# S7CAS-PLEIADES-CARTE-MERE_P02_POWER_CARR.net
KiCad netlist of a schematic drawn in Altium Designer
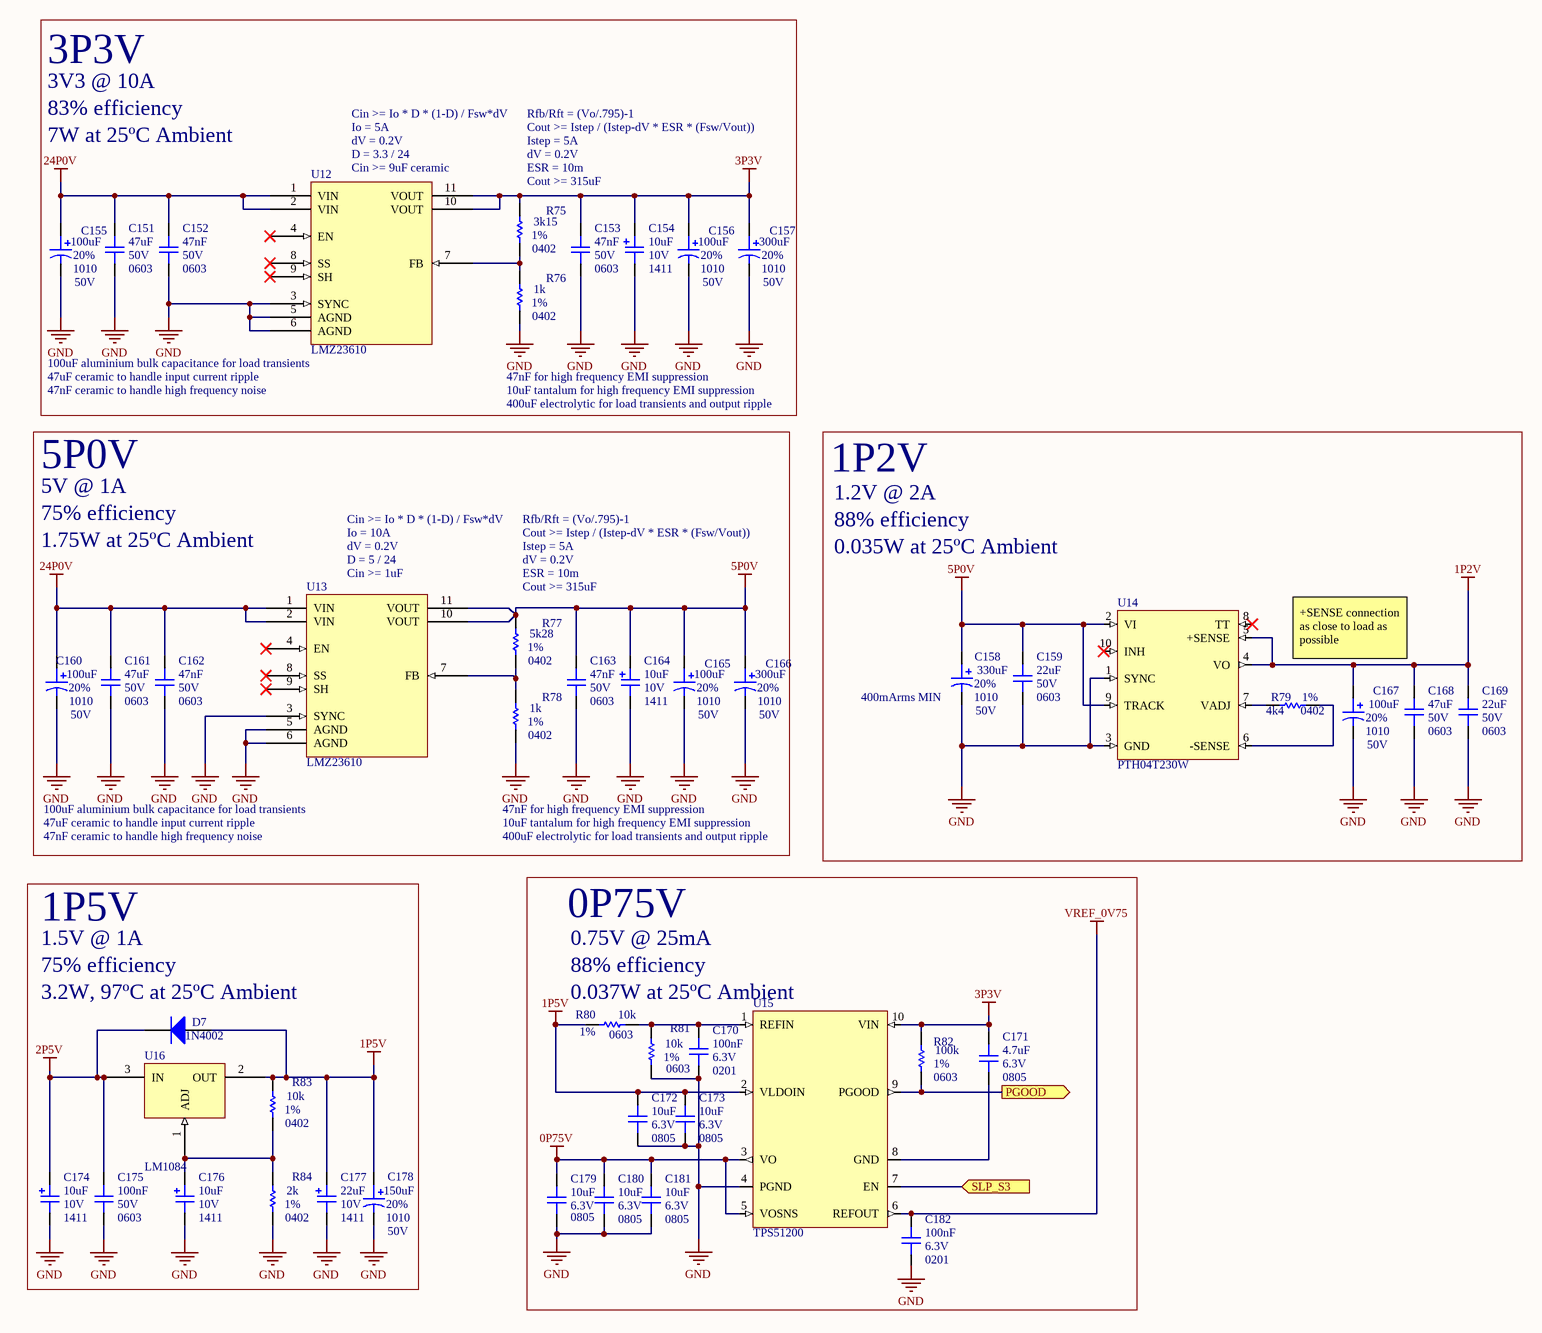
[diagram p0: S7CAS-PLEIADES-CARTE-MERE_P02_POWER_CARRIER.SchDoc]

(export (version "E")
  (design (tool "Eeschema 10.0.6"))
  (components
    (comp (ref "C151")
      (value "47uF")
      (footprint "CAP_0603")
      (description "CAP - 0603")
      (fields
        (field (name "VOLTAGE") "50V")
        (field (name "PACKAGE") "0603")
        (field (name "CREATEDBY") "Jonathan Bouchard")
      )
      (libsource (lib "S7CAS_Lib2019_REV1_00") (part "CAP - 0603"))
    )
    (comp (ref "C152")
      (value "47nF")
      (footprint "CAP_0603")
      (description "CAP - 0603")
      (fields
        (field (name "VOLTAGE") "50V")
        (field (name "PACKAGE") "0603")
        (field (name "CREATEDBY") "Jonathan Bouchard")
      )
      (libsource (lib "S7CAS_Lib2019_REV1_00") (part "CAP - 0603"))
    )
    (comp (ref "C153")
      (value "47nF")
      (footprint "CAP_0603")
      (description "CAP - 0603")
      (fields
        (field (name "VOLTAGE") "50V")
        (field (name "PACKAGE") "0603")
        (field (name "CREATEDBY") "Jonathan Bouchard")
      )
      (libsource (lib "S7CAS_Lib2019_REV1_00") (part "CAP - 0603"))
    )
    (comp (ref "C154")
      (value "10uF")
      (footprint "CAP_TAN_1411(B)")
      (description "CAP - TANTALUM - 1411")
      (fields
        (field (name "VOLTAGE") "10V")
        (field (name "PACKAGE") "1411")
        (field (name "Comment") "CAP - TANTALUM - CASE B")
        (field (name "CREATEDBY") "Jonathan Bouchard")
      )
      (libsource (lib "S7CAS_Lib2019_REV1_00") (part "CAP_TANT_1411(B)"))
    )
    (comp (ref "C155")
      (value "100uF")
      (footprint "CAP_ALU_1010_vishay")
      (description "CAP - ALU 100uF 20% 50V - 1010")
      (fields
        (field (name "MFG") "Vishay Dale")
        (field (name "MFG PART NUMBER") "MAL215099101E3")
        (field (name "VOLTAGE") "50V")
        (field (name "PACKAGE") "1010")
        (field (name "PRECISION") "20%")
        (field (name "CREATEDBY") "Jonathan Bouchard")
      )
      (libsource (lib "S7CAS_Lib2019_REV1_00") (part "CAP_ALU_MAL215099101E3"))
    )
    (comp (ref "C156")
      (value "100uF")
      (footprint "CAP_ALU_1010_vishay")
      (description "CAP - ALU 100uF 20% 50V - 1010")
      (fields
        (field (name "MFG") "Vishay Dale")
        (field (name "MFG PART NUMBER") "MAL215099101E3")
        (field (name "VOLTAGE") "50V")
        (field (name "PACKAGE") "1010")
        (field (name "PRECISION") "20%")
        (field (name "CREATEDBY") "Jonathan Bouchard")
      )
      (libsource (lib "S7CAS_Lib2019_REV1_00") (part "CAP_ALU_MAL215099101E3"))
    )
    (comp (ref "C157")
      (value "300uF")
      (footprint "CAP_ALU_1010_vishay")
      (description "CAP - ALU 100uF 20% 50V - 1010")
      (fields
        (field (name "MFG") "Vishay Dale")
        (field (name "MFG PART NUMBER") "MAL215099101E3")
        (field (name "VOLTAGE") "50V")
        (field (name "PACKAGE") "1010")
        (field (name "PRECISION") "20%")
        (field (name "CREATEDBY") "Jonathan Bouchard")
      )
      (libsource (lib "S7CAS_Lib2019_REV1_00") (part "CAP_ALU_MAL215099101E3"))
    )
    (comp (ref "C158")
      (value "330uF")
      (footprint "CAP_ALU_1010_vishay")
      (description "CAP - ALU 100uF 20% 50V - 1010")
      (fields
        (field (name "MFG") "Vishay Dale")
        (field (name "MFG PART NUMBER") "MAL215099101E3")
        (field (name "VOLTAGE") "50V")
        (field (name "PACKAGE") "1010")
        (field (name "PRECISION") "20%")
        (field (name "CREATEDBY") "Jonathan Bouchard")
      )
      (libsource (lib "S7CAS_Lib2019_REV1_00") (part "CAP_ALU_MAL215099101E3"))
    )
    (comp (ref "C159")
      (value "22uF")
      (footprint "CAP_0603")
      (description "CAP - 0603")
      (fields
        (field (name "VOLTAGE") "50V")
        (field (name "PACKAGE") "0603")
        (field (name "CREATEDBY") "Jonathan Bouchard")
      )
      (libsource (lib "S7CAS_Lib2019_REV1_00") (part "CAP - 0603"))
    )
    (comp (ref "C160")
      (value "100uF")
      (footprint "CAP_ALU_1010_vishay")
      (description "CAP - ALU 100uF 20% 50V - 1010")
      (fields
        (field (name "MFG") "Vishay Dale")
        (field (name "MFG PART NUMBER") "MAL215099101E3")
        (field (name "VOLTAGE") "50V")
        (field (name "PACKAGE") "1010")
        (field (name "PRECISION") "20%")
        (field (name "CREATEDBY") "Jonathan Bouchard")
      )
      (libsource (lib "S7CAS_Lib2019_REV1_00") (part "CAP_ALU_MAL215099101E3"))
    )
    (comp (ref "C161")
      (value "47uF")
      (footprint "CAP_0603")
      (description "CAP - 0603")
      (fields
        (field (name "VOLTAGE") "50V")
        (field (name "PACKAGE") "0603")
        (field (name "CREATEDBY") "Jonathan Bouchard")
      )
      (libsource (lib "S7CAS_Lib2019_REV1_00") (part "CAP - 0603"))
    )
    (comp (ref "C162")
      (value "47nF")
      (footprint "CAP_0603")
      (description "CAP - 0603")
      (fields
        (field (name "VOLTAGE") "50V")
        (field (name "PACKAGE") "0603")
        (field (name "CREATEDBY") "Jonathan Bouchard")
      )
      (libsource (lib "S7CAS_Lib2019_REV1_00") (part "CAP - 0603"))
    )
    (comp (ref "C163")
      (value "47nF")
      (footprint "CAP_0603")
      (description "CAP - 0603")
      (fields
        (field (name "VOLTAGE") "50V")
        (field (name "PACKAGE") "0603")
        (field (name "CREATEDBY") "Jonathan Bouchard")
      )
      (libsource (lib "S7CAS_Lib2019_REV1_00") (part "CAP - 0603"))
    )
    (comp (ref "C164")
      (value "10uF")
      (footprint "CAP_TAN_1411(B)")
      (description "CAP - TANTALUM - 1411")
      (fields
        (field (name "VOLTAGE") "10V")
        (field (name "PACKAGE") "1411")
        (field (name "Comment") "CAP - TANTALUM - CASE B")
        (field (name "CREATEDBY") "Jonathan Bouchard")
      )
      (libsource (lib "S7CAS_Lib2019_REV1_00") (part "CAP_TANT_1411(B)"))
    )
    (comp (ref "C165")
      (value "100uF")
      (footprint "CAP_ALU_1010_vishay")
      (description "CAP - ALU 100uF 20% 50V - 1010")
      (fields
        (field (name "MFG") "Vishay Dale")
        (field (name "MFG PART NUMBER") "MAL215099101E3")
        (field (name "VOLTAGE") "50V")
        (field (name "PACKAGE") "1010")
        (field (name "PRECISION") "20%")
        (field (name "CREATEDBY") "Jonathan Bouchard")
      )
      (libsource (lib "S7CAS_Lib2019_REV1_00") (part "CAP_ALU_MAL215099101E3"))
    )
    (comp (ref "C166")
      (value "300uF")
      (footprint "CAP_ALU_1010_vishay")
      (description "CAP - ALU 100uF 20% 50V - 1010")
      (fields
        (field (name "MFG") "Vishay Dale")
        (field (name "MFG PART NUMBER") "MAL215099101E3")
        (field (name "VOLTAGE") "50V")
        (field (name "PACKAGE") "1010")
        (field (name "PRECISION") "20%")
        (field (name "CREATEDBY") "Jonathan Bouchard")
      )
      (libsource (lib "S7CAS_Lib2019_REV1_00") (part "CAP_ALU_MAL215099101E3"))
    )
    (comp (ref "C167")
      (value "100uF")
      (footprint "CAP_ALU_1010_vishay")
      (description "CAP - ALU 100uF 20% 50V - 1010")
      (fields
        (field (name "MFG") "Vishay Dale")
        (field (name "MFG PART NUMBER") "MAL215099101E3")
        (field (name "VOLTAGE") "50V")
        (field (name "PACKAGE") "1010")
        (field (name "PRECISION") "20%")
        (field (name "CREATEDBY") "Jonathan Bouchard")
      )
      (libsource (lib "S7CAS_Lib2019_REV1_00") (part "CAP_ALU_MAL215099101E3"))
    )
    (comp (ref "C168")
      (value "47uF")
      (footprint "CAP_0603")
      (description "CAP - 0603")
      (fields
        (field (name "VOLTAGE") "50V")
        (field (name "PACKAGE") "0603")
        (field (name "CREATEDBY") "Jonathan Bouchard")
      )
      (libsource (lib "S7CAS_Lib2019_REV1_00") (part "CAP - 0603"))
    )
    (comp (ref "C169")
      (value "22uF")
      (footprint "CAP_0603")
      (description "CAP - 0603")
      (fields
        (field (name "VOLTAGE") "50V")
        (field (name "PACKAGE") "0603")
        (field (name "CREATEDBY") "Jonathan Bouchard")
      )
      (libsource (lib "S7CAS_Lib2019_REV1_00") (part "CAP - 0603"))
    )
    (comp (ref "C170")
      (value "100nF")
      (footprint "CAP_0201")
      (description "CAP - 0201")
      (fields
        (field (name "VOLTAGE") "6.3V")
        (field (name "PACKAGE") "0201")
        (field (name "CREATEDBY") "Jonathan Bouchard")
      )
      (libsource (lib "S7CAS_Lib2019_REV1_00") (part "CAP - 0201"))
    )
    (comp (ref "C171")
      (value "4.7uF")
      (footprint "CAP_0805")
      (description "CAP - 0805")
      (fields
        (field (name "VOLTAGE") "6.3V")
        (field (name "PACKAGE") "0805")
        (field (name "CREATEDBY") "Jonathan Bouchard")
      )
      (libsource (lib "S7CAS_Lib2019_REV1_00") (part "CAP - 0805"))
    )
    (comp (ref "C172")
      (value "10uF")
      (footprint "CAP_0805")
      (description "CAP - 0805")
      (fields
        (field (name "VOLTAGE") "6.3V")
        (field (name "PACKAGE") "0805")
        (field (name "CREATEDBY") "Jonathan Bouchard")
      )
      (libsource (lib "S7CAS_Lib2019_REV1_00") (part "CAP - 0805"))
    )
    (comp (ref "C173")
      (value "10uF")
      (footprint "CAP_0805")
      (description "CAP - 0805")
      (fields
        (field (name "VOLTAGE") "6.3V")
        (field (name "PACKAGE") "0805")
        (field (name "CREATEDBY") "Jonathan Bouchard")
      )
      (libsource (lib "S7CAS_Lib2019_REV1_00") (part "CAP - 0805"))
    )
    (comp (ref "C174")
      (value "10uF")
      (footprint "CAP_TAN_1411(B)")
      (description "CAP - TANTALUM - 1411")
      (fields
        (field (name "VOLTAGE") "10V")
        (field (name "PACKAGE") "1411")
        (field (name "Comment") "CAP - TANTALUM - CASE B")
        (field (name "CREATEDBY") "Jonathan Bouchard")
      )
      (libsource (lib "S7CAS_Lib2019_REV1_00") (part "CAP_TANT_1411(B)"))
    )
    (comp (ref "C175")
      (value "100nF")
      (footprint "CAP_0603")
      (description "CAP - 0603")
      (fields
        (field (name "VOLTAGE") "50V")
        (field (name "PACKAGE") "0603")
        (field (name "CREATEDBY") "Jonathan Bouchard")
      )
      (libsource (lib "S7CAS_Lib2019_REV1_00") (part "CAP - 0603"))
    )
    (comp (ref "C176")
      (value "10uF")
      (footprint "CAP_TAN_1411(B)")
      (description "CAP - TANTALUM - 1411")
      (fields
        (field (name "VOLTAGE") "10V")
        (field (name "PACKAGE") "1411")
        (field (name "Comment") "CAP - TANTALUM - CASE B")
        (field (name "CREATEDBY") "Jonathan Bouchard")
      )
      (libsource (lib "S7CAS_Lib2019_REV1_00") (part "CAP_TANT_1411(B)"))
    )
    (comp (ref "C177")
      (value "22uF")
      (footprint "CAP_TAN_1411(B)")
      (description "CAP - TANTALUM - 1411")
      (fields
        (field (name "VOLTAGE") "10V")
        (field (name "PACKAGE") "1411")
        (field (name "Comment") "CAP - TANTALUM - CASE B")
        (field (name "CREATEDBY") "Jonathan Bouchard")
      )
      (libsource (lib "S7CAS_Lib2019_REV1_00") (part "CAP_TANT_1411(B)"))
    )
    (comp (ref "C178")
      (value "150uF")
      (footprint "CAP_ALU_1010_vishay")
      (description "CAP - ALU 100uF 20% 50V - 1010")
      (fields
        (field (name "MFG") "Vishay Dale")
        (field (name "MFG PART NUMBER") "MAL215099101E3")
        (field (name "VOLTAGE") "50V")
        (field (name "PACKAGE") "1010")
        (field (name "PRECISION") "20%")
        (field (name "CREATEDBY") "Jonathan Bouchard")
      )
      (libsource (lib "S7CAS_Lib2019_REV1_00") (part "CAP_ALU_MAL215099101E3"))
    )
    (comp (ref "C179")
      (value "10uF")
      (footprint "CAP_0805")
      (description "CAP - 0805")
      (fields
        (field (name "VOLTAGE") "6.3V")
        (field (name "PACKAGE") "0805")
        (field (name "CREATEDBY") "Jonathan Bouchard")
      )
      (libsource (lib "S7CAS_Lib2019_REV1_00") (part "CAP - 0805"))
    )
    (comp (ref "C180")
      (value "10uF")
      (footprint "CAP_0805")
      (description "CAP - 0805")
      (fields
        (field (name "VOLTAGE") "6.3V")
        (field (name "PACKAGE") "0805")
        (field (name "CREATEDBY") "Jonathan Bouchard")
      )
      (libsource (lib "S7CAS_Lib2019_REV1_00") (part "CAP - 0805"))
    )
    (comp (ref "C181")
      (value "10uF")
      (footprint "CAP_0805")
      (description "CAP - 0805")
      (fields
        (field (name "VOLTAGE") "6.3V")
        (field (name "PACKAGE") "0805")
        (field (name "CREATEDBY") "Jonathan Bouchard")
      )
      (libsource (lib "S7CAS_Lib2019_REV1_00") (part "CAP - 0805"))
    )
    (comp (ref "C182")
      (value "100nF")
      (footprint "CAP_0201")
      (description "CAP - 0201")
      (fields
        (field (name "VOLTAGE") "6.3V")
        (field (name "PACKAGE") "0201")
        (field (name "CREATEDBY") "Jonathan Bouchard")
      )
      (libsource (lib "S7CAS_Lib2019_REV1_00") (part "CAP - 0201"))
    )
    (comp (ref "D7")
      (value "1N4002")
      (footprint "DO-41")
      (description "1 Amp General Purpose Rectifier")
      (fields (field (name "PUBLISHER") "Altium Limited"))
      (libsource (lib "Miscellaneous Devices") (part "Diode 1N4002"))
    )
    (comp (ref "R75")
      (value "3k15")
      (footprint "RES_0402")
      (description "RES - 0402")
      (fields
        (field (name "VOLTAGE") "50V")
        (field (name "POWER") "1/16W")
        (field (name "PACKAGE") "0402")
        (field (name "PRECISION") "1%")
        (field (name "CREATEDBY") "Jonathan Bouchard")
      )
      (libsource (lib "S7CAS_Lib2019_REV1_00") (part "RES - 0402"))
    )
    (comp (ref "R76")
      (value "1k")
      (footprint "RES_0402")
      (description "RES - 0402")
      (fields
        (field (name "VOLTAGE") "50V")
        (field (name "POWER") "1/16W")
        (field (name "PACKAGE") "0402")
        (field (name "PRECISION") "1%")
        (field (name "CREATEDBY") "Jonathan Bouchard")
      )
      (libsource (lib "S7CAS_Lib2019_REV1_00") (part "RES - 0402"))
    )
    (comp (ref "R77")
      (value "5k28")
      (footprint "RES_0402")
      (description "RES - 0402")
      (fields
        (field (name "VOLTAGE") "50V")
        (field (name "POWER") "1/16W")
        (field (name "PACKAGE") "0402")
        (field (name "PRECISION") "1%")
        (field (name "CREATEDBY") "Jonathan Bouchard")
      )
      (libsource (lib "S7CAS_Lib2019_REV1_00") (part "RES - 0402"))
    )
    (comp (ref "R78")
      (value "1k")
      (footprint "RES_0402")
      (description "RES - 0402")
      (fields
        (field (name "VOLTAGE") "50V")
        (field (name "POWER") "1/16W")
        (field (name "PACKAGE") "0402")
        (field (name "PRECISION") "1%")
        (field (name "CREATEDBY") "Jonathan Bouchard")
      )
      (libsource (lib "S7CAS_Lib2019_REV1_00") (part "RES - 0402"))
    )
    (comp (ref "R79")
      (value "4k4")
      (footprint "RES_0402")
      (description "RES - 0402")
      (fields
        (field (name "VOLTAGE") "50V")
        (field (name "POWER") "1/16W")
        (field (name "PACKAGE") "0402")
        (field (name "PRECISION") "1%")
        (field (name "CREATEDBY") "Jonathan Bouchard")
      )
      (libsource (lib "S7CAS_Lib2019_REV1_00") (part "RES - 0402"))
    )
    (comp (ref "R80")
      (value "10k")
      (footprint "RES_0603")
      (description "RES - 0603")
      (fields
        (field (name "PACKAGE") "0603")
        (field (name "PRECISION") "1%")
        (field (name "CREATEDBY") "Jonathan Bouchard")
      )
      (libsource (lib "S7CAS_Lib2019_REV1_00") (part "RES - 0603"))
    )
    (comp (ref "R81")
      (value "10k")
      (footprint "RES_0603")
      (description "RES - 0603")
      (fields
        (field (name "PACKAGE") "0603")
        (field (name "PRECISION") "1%")
        (field (name "CREATEDBY") "Jonathan Bouchard")
      )
      (libsource (lib "S7CAS_Lib2019_REV1_00") (part "RES - 0603"))
    )
    (comp (ref "R82")
      (value "100k")
      (footprint "RES_0603")
      (description "RES - 0603")
      (fields
        (field (name "PACKAGE") "0603")
        (field (name "PRECISION") "1%")
        (field (name "CREATEDBY") "Jonathan Bouchard")
      )
      (libsource (lib "S7CAS_Lib2019_REV1_00") (part "RES - 0603"))
    )
    (comp (ref "R83")
      (value "10k")
      (footprint "RES_0402")
      (description "RES - 0402")
      (fields
        (field (name "VOLTAGE") "50V")
        (field (name "POWER") "1/16W")
        (field (name "PACKAGE") "0402")
        (field (name "PRECISION") "1%")
        (field (name "CREATEDBY") "Jonathan Bouchard")
      )
      (libsource (lib "S7CAS_Lib2019_REV1_00") (part "RES - 0402"))
    )
    (comp (ref "R84")
      (value "2k")
      (footprint "RES_0402")
      (description "RES - 0402")
      (fields
        (field (name "VOLTAGE") "50V")
        (field (name "POWER") "1/16W")
        (field (name "PACKAGE") "0402")
        (field (name "PRECISION") "1%")
        (field (name "CREATEDBY") "Jonathan Bouchard")
      )
      (libsource (lib "S7CAS_Lib2019_REV1_00") (part "RES - 0402"))
    )
    (comp (ref "U12") (value "LMZ23610") (libsource (lib "lib_JF") (part "LMZ23610")))
    (comp (ref "U13") (value "LMZ23610") (libsource (lib "lib_JF") (part "LMZ23610")))
    (comp (ref "U14")
      (value "PTH04T230W")
      (description "XXX - Description - Package")
      (libsource (lib "lib_JF") (part "PTH04T230W"))
    )
    (comp (ref "U15")
      (value "TPS51200")
      (description "TPS51200\r\nSink and Source\r\nDDR Termination\r\nRegulator")
      (libsource (lib "lib_Thom") (part "TPS51200"))
    )
    (comp (ref "U16") (value "LM1084") (libsource (lib "lib_JF") (part "LM1084")))
  )
  (nets
    (net (code "1") (name "/PGOOD") (class "Default")
      (node (ref "R82") (pin "1") (pinfunction "1_1") (pintype "passive"))
      (node (ref "U15") (pin "9") (pinfunction "PGOOD_9") (pintype "output"))
    )
    (net (code "2") (name "/SLP_S3") (class "Default")
      (node (ref "U15") (pin "7") (pinfunction "EN_7") (pintype "passive"))
    )
    (net (code "3") (name "0P75V") (class "Default")
      (node (ref "C179") (pin "2") (pinfunction "2_2") (pintype "passive"))
      (node (ref "C180") (pin "2") (pinfunction "2_2") (pintype "passive"))
      (node (ref "C181") (pin "2") (pinfunction "2_2") (pintype "passive"))
      (node (ref "U15") (pin "3") (pinfunction "VO_3") (pintype "output"))
      (node (ref "U15") (pin "5") (pinfunction "VOSNS_5") (pintype "input"))
    )
    (net (code "4") (name "1P2V") (class "Default")
      (node (ref "C167") (pin "1") (pinfunction "1_1") (pintype "passive"))
      (node (ref "C168") (pin "2") (pinfunction "2_2") (pintype "passive"))
      (node (ref "C169") (pin "2") (pinfunction "2_2") (pintype "passive"))
      (node (ref "U14") (pin "4") (pinfunction "VO_4") (pintype "output"))
      (node (ref "U14") (pin "5") (pinfunction "+SENSE_5") (pintype "input"))
    )
    (net (code "5") (name "1P5V") (class "Default")
      (node (ref "C172") (pin "2") (pinfunction "2_2") (pintype "passive"))
      (node (ref "C173") (pin "2") (pinfunction "2_2") (pintype "passive"))
      (node (ref "C177") (pin "2") (pinfunction "2_2") (pintype "passive"))
      (node (ref "C178") (pin "1") (pinfunction "1_1") (pintype "passive"))
      (node (ref "D7") (pin "1") (pinfunction "A_1") (pintype "passive"))
      (node (ref "R80") (pin "2") (pinfunction "2_2") (pintype "passive"))
      (node (ref "R83") (pin "2") (pinfunction "2_2") (pintype "passive"))
      (node (ref "U15") (pin "2") (pinfunction "VLDOIN_2") (pintype "input"))
      (node (ref "U16") (pin "2") (pinfunction "OUT_2") (pintype "power_in"))
    )
    (net (code "6") (name "2P5V") (class "Default")
      (node (ref "C174") (pin "2") (pinfunction "2_2") (pintype "passive"))
      (node (ref "C175") (pin "2") (pinfunction "2_2") (pintype "passive"))
      (node (ref "D7") (pin "2") (pinfunction "K_2") (pintype "passive"))
      (node (ref "U16") (pin "3") (pinfunction "IN_3") (pintype "power_in"))
    )
    (net (code "7") (name "3P3V") (class "Default")
      (node (ref "C153") (pin "2") (pinfunction "2_2") (pintype "passive"))
      (node (ref "C154") (pin "2") (pinfunction "2_2") (pintype "passive"))
      (node (ref "C156") (pin "1") (pinfunction "1_1") (pintype "passive"))
      (node (ref "C157") (pin "1") (pinfunction "1_1") (pintype "passive"))
      (node (ref "C171") (pin "2") (pinfunction "2_2") (pintype "passive"))
      (node (ref "R75") (pin "2") (pinfunction "2_2") (pintype "passive"))
      (node (ref "R82") (pin "2") (pinfunction "2_2") (pintype "passive"))
      (node (ref "U12") (pin "10") (pinfunction "VOUT_10") (pintype "power_in"))
      (node (ref "U12") (pin "11") (pinfunction "VOUT_11") (pintype "power_in"))
      (node (ref "U15") (pin "10") (pinfunction "VIN_10") (pintype "input"))
    )
    (net (code "8") (name "5P0V") (class "Default")
      (node (ref "C158") (pin "1") (pinfunction "1_1") (pintype "passive"))
      (node (ref "C159") (pin "2") (pinfunction "2_2") (pintype "passive"))
      (node (ref "C163") (pin "2") (pinfunction "2_2") (pintype "passive"))
      (node (ref "C164") (pin "2") (pinfunction "2_2") (pintype "passive"))
      (node (ref "C165") (pin "1") (pinfunction "1_1") (pintype "passive"))
      (node (ref "C166") (pin "1") (pinfunction "1_1") (pintype "passive"))
      (node (ref "R77") (pin "2") (pinfunction "2_2") (pintype "passive"))
      (node (ref "U13") (pin "10") (pinfunction "VOUT_10") (pintype "power_in"))
      (node (ref "U13") (pin "11") (pinfunction "VOUT_11") (pintype "power_in"))
      (node (ref "U14") (pin "2") (pinfunction "VI_2") (pintype "input"))
      (node (ref "U14") (pin "9") (pinfunction "TRACK_9") (pintype "input"))
    )
    (net (code "9") (name "24P0V") (class "Default")
      (node (ref "C151") (pin "2") (pinfunction "2_2") (pintype "passive"))
      (node (ref "C152") (pin "2") (pinfunction "2_2") (pintype "passive"))
      (node (ref "C155") (pin "1") (pinfunction "1_1") (pintype "passive"))
      (node (ref "C160") (pin "1") (pinfunction "1_1") (pintype "passive"))
      (node (ref "C161") (pin "2") (pinfunction "2_2") (pintype "passive"))
      (node (ref "C162") (pin "2") (pinfunction "2_2") (pintype "passive"))
      (node (ref "U12") (pin "1") (pinfunction "VIN_1") (pintype "power_in"))
      (node (ref "U12") (pin "2") (pinfunction "VIN_2") (pintype "power_in"))
      (node (ref "U13") (pin "1") (pinfunction "VIN_1") (pintype "power_in"))
      (node (ref "U13") (pin "2") (pinfunction "VIN_2") (pintype "power_in"))
    )
    (net (code "10") (name "GND") (class "Default")
      (node (ref "C151") (pin "1") (pinfunction "1_1") (pintype "passive"))
      (node (ref "C152") (pin "1") (pinfunction "1_1") (pintype "passive"))
      (node (ref "C153") (pin "1") (pinfunction "1_1") (pintype "passive"))
      (node (ref "C154") (pin "1") (pinfunction "1_1") (pintype "passive"))
      (node (ref "C155") (pin "2") (pinfunction "2_2") (pintype "passive"))
      (node (ref "C156") (pin "2") (pinfunction "2_2") (pintype "passive"))
      (node (ref "C157") (pin "2") (pinfunction "2_2") (pintype "passive"))
      (node (ref "C158") (pin "2") (pinfunction "2_2") (pintype "passive"))
      (node (ref "C159") (pin "1") (pinfunction "1_1") (pintype "passive"))
      (node (ref "C160") (pin "2") (pinfunction "2_2") (pintype "passive"))
      (node (ref "C161") (pin "1") (pinfunction "1_1") (pintype "passive"))
      (node (ref "C162") (pin "1") (pinfunction "1_1") (pintype "passive"))
      (node (ref "C163") (pin "1") (pinfunction "1_1") (pintype "passive"))
      (node (ref "C164") (pin "1") (pinfunction "1_1") (pintype "passive"))
      (node (ref "C165") (pin "2") (pinfunction "2_2") (pintype "passive"))
      (node (ref "C166") (pin "2") (pinfunction "2_2") (pintype "passive"))
      (node (ref "C167") (pin "2") (pinfunction "2_2") (pintype "passive"))
      (node (ref "C168") (pin "1") (pinfunction "1_1") (pintype "passive"))
      (node (ref "C169") (pin "1") (pinfunction "1_1") (pintype "passive"))
      (node (ref "C170") (pin "1") (pinfunction "1_1") (pintype "passive"))
      (node (ref "C172") (pin "1") (pinfunction "1_1") (pintype "passive"))
      (node (ref "C173") (pin "1") (pinfunction "1_1") (pintype "passive"))
      (node (ref "C174") (pin "1") (pinfunction "1_1") (pintype "passive"))
      (node (ref "C175") (pin "1") (pinfunction "1_1") (pintype "passive"))
      (node (ref "C176") (pin "1") (pinfunction "1_1") (pintype "passive"))
      (node (ref "C177") (pin "1") (pinfunction "1_1") (pintype "passive"))
      (node (ref "C178") (pin "2") (pinfunction "2_2") (pintype "passive"))
      (node (ref "C179") (pin "1") (pinfunction "1_1") (pintype "passive"))
      (node (ref "C180") (pin "1") (pinfunction "1_1") (pintype "passive"))
      (node (ref "C181") (pin "1") (pinfunction "1_1") (pintype "passive"))
      (node (ref "R76") (pin "1") (pinfunction "1_1") (pintype "passive"))
      (node (ref "R78") (pin "1") (pinfunction "1_1") (pintype "passive"))
      (node (ref "R81") (pin "1") (pinfunction "1_1") (pintype "passive"))
      (node (ref "R84") (pin "1") (pinfunction "1_1") (pintype "passive"))
      (node (ref "U12") (pin "3") (pinfunction "SYNC_3") (pintype "input"))
      (node (ref "U12") (pin "5") (pinfunction "AGND_5") (pintype "power_in"))
      (node (ref "U12") (pin "6") (pinfunction "AGND_6") (pintype "power_in"))
      (node (ref "U13") (pin "3") (pinfunction "SYNC_3") (pintype "input"))
      (node (ref "U13") (pin "5") (pinfunction "AGND_5") (pintype "power_in"))
      (node (ref "U13") (pin "6") (pinfunction "AGND_6") (pintype "power_in"))
      (node (ref "U14") (pin "1") (pinfunction "SYNC_1") (pintype "input"))
      (node (ref "U14") (pin "3") (pinfunction "GND_3") (pintype "input"))
      (node (ref "U15") (pin "4") (pinfunction "PGND_4") (pintype "power_in"))
    )
    (net (code "11") (name "Net-(U12-FB)") (class "Default")
      (node (ref "R75") (pin "1") (pinfunction "1_1") (pintype "passive"))
      (node (ref "R76") (pin "2") (pinfunction "2_2") (pintype "passive"))
      (node (ref "U12") (pin "7") (pinfunction "FB_7") (pintype "input"))
    )
    (net (code "12") (name "Net-(U13-FB)") (class "Default")
      (node (ref "R77") (pin "1") (pinfunction "1_1") (pintype "passive"))
      (node (ref "R78") (pin "2") (pinfunction "2_2") (pintype "passive"))
      (node (ref "U13") (pin "7") (pinfunction "FB_7") (pintype "input"))
    )
    (net (code "13") (name "Net-(U14--SENSE)") (class "Default")
      (node (ref "R79") (pin "1") (pinfunction "1_1") (pintype "passive"))
      (node (ref "U14") (pin "6") (pinfunction "-SENSE_6") (pintype "input"))
    )
    (net (code "14") (name "Net-(U14-VADJ)") (class "Default")
      (node (ref "R79") (pin "2") (pinfunction "2_2") (pintype "passive"))
      (node (ref "U14") (pin "7") (pinfunction "VADJ_7") (pintype "input"))
    )
    (net (code "15") (name "Net-(U15-GND)") (class "Default")
      (node (ref "C171") (pin "1") (pinfunction "1_1") (pintype "passive"))
      (node (ref "U15") (pin "8") (pinfunction "GND_8") (pintype "power_in"))
    )
    (net (code "16") (name "Net-(U15-REFIN)") (class "Default")
      (node (ref "C170") (pin "2") (pinfunction "2_2") (pintype "passive"))
      (node (ref "R80") (pin "1") (pinfunction "1_1") (pintype "passive"))
      (node (ref "R81") (pin "2") (pinfunction "2_2") (pintype "passive"))
      (node (ref "U15") (pin "1") (pinfunction "REFIN_1") (pintype "input"))
    )
    (net (code "17") (name "Net-(U16-ADJ)") (class "Default")
      (node (ref "C176") (pin "2") (pinfunction "2_2") (pintype "passive"))
      (node (ref "R83") (pin "1") (pinfunction "1_1") (pintype "passive"))
      (node (ref "R84") (pin "2") (pinfunction "2_2") (pintype "passive"))
      (node (ref "U16") (pin "1") (pinfunction "ADJ_1") (pintype "input"))
    )
    (net (code "18") (name "VREF_0V75") (class "Default")
      (node (ref "C182") (pin "2") (pinfunction "2_2") (pintype "passive"))
      (node (ref "U15") (pin "6") (pinfunction "REFOUT_6") (pintype "output"))
    )
    (net (code "19") (name "unconnected-(C182-Pad1)") (class "Default")
      (node (ref "C182") (pin "1") (pinfunction "1_1") (pintype "passive"))
    )
    (net (code "20") (name "unconnected-(U12-EN-Pad4)") (class "Default")
      (node (ref "U12") (pin "4") (pinfunction "EN_4") (pintype "input+no_connect"))
    )
    (net (code "21") (name "unconnected-(U12-SH-Pad9)") (class "Default")
      (node (ref "U12") (pin "9") (pinfunction "SH_9") (pintype "input+no_connect"))
    )
    (net (code "22") (name "unconnected-(U12-SS-Pad8)") (class "Default")
      (node (ref "U12") (pin "8") (pinfunction "SS_8") (pintype "input+no_connect"))
    )
    (net (code "23") (name "unconnected-(U13-EN-Pad4)") (class "Default")
      (node (ref "U13") (pin "4") (pinfunction "EN_4") (pintype "input+no_connect"))
    )
    (net (code "24") (name "unconnected-(U13-SH-Pad9)") (class "Default")
      (node (ref "U13") (pin "9") (pinfunction "SH_9") (pintype "input+no_connect"))
    )
    (net (code "25") (name "unconnected-(U13-SS-Pad8)") (class "Default")
      (node (ref "U13") (pin "8") (pinfunction "SS_8") (pintype "input+no_connect"))
    )
    (net (code "26") (name "unconnected-(U14-INH-Pad10)") (class "Default")
      (node (ref "U14") (pin "10") (pinfunction "INH_10") (pintype "input+no_connect"))
    )
    (net (code "27") (name "unconnected-(U14-TT-Pad8)") (class "Default")
      (node (ref "U14") (pin "8") (pinfunction "TT_8") (pintype "input+no_connect"))
    )
  )
)
